# FiltreFSK.net
KiCad netlist of a schematic drawn in EAGLE
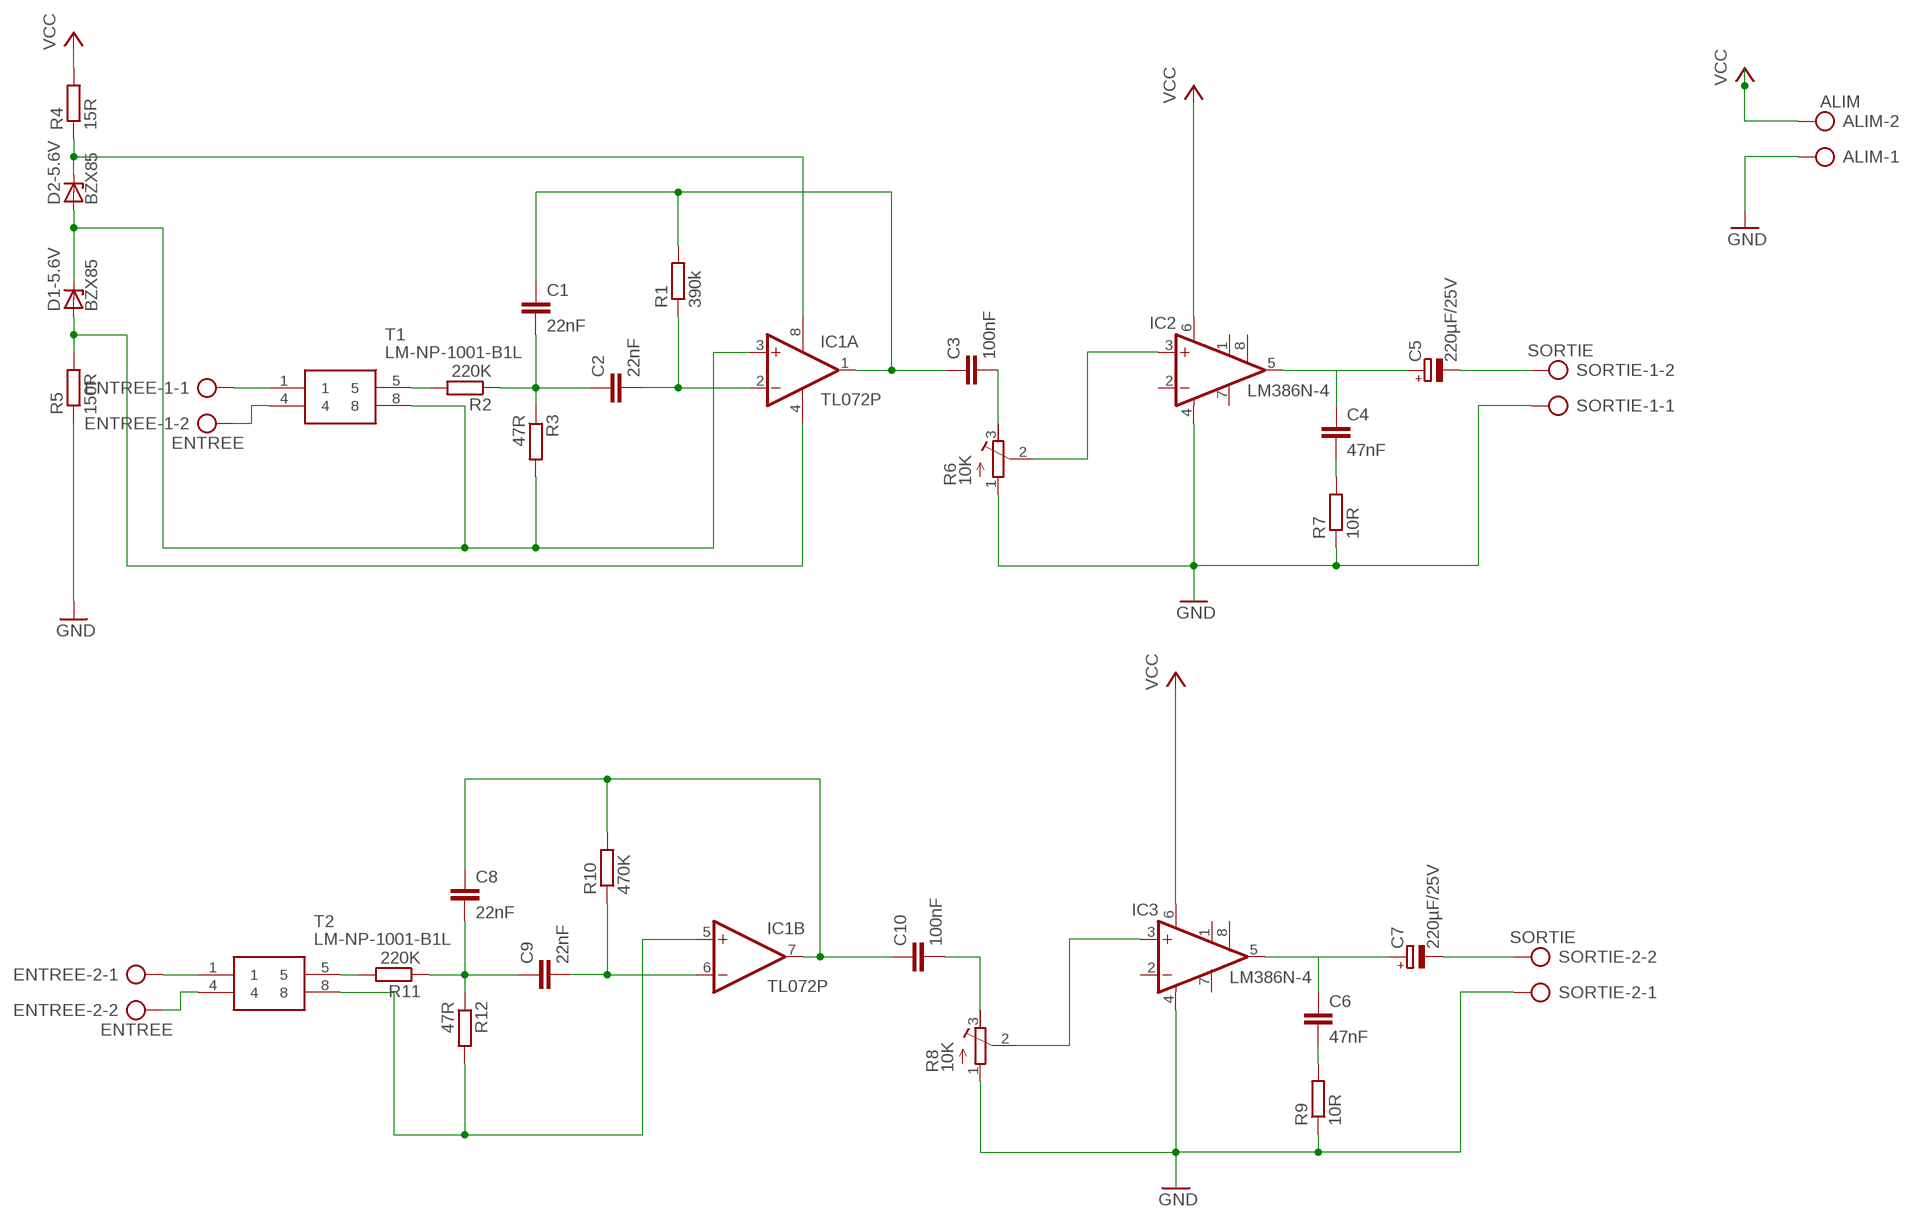
[diagram p0: schematic, sheet 1]

(export (version "E")
  (design (tool "Eeschema 10.0.6"))
  (components
    (comp (ref "ALIM")
      (value "ALIM")
      (footprint "eagle-import:AK500_2-H")
      (libsource (lib "eagle-import") (part "AK500/2-H"))
    )
    (comp (ref "C1")
      (value "22nF")
      (footprint "eagle-import:C050-025X075")
      (libsource (lib "eagle-import") (part "C-EU050-025X075"))
    )
    (comp (ref "C2")
      (value "22nF")
      (footprint "eagle-import:C050-025X075")
      (libsource (lib "eagle-import") (part "C-EU050-025X075"))
    )
    (comp (ref "C3")
      (value "100nF")
      (footprint "eagle-import:C075-042X103")
      (libsource (lib "eagle-import") (part "C-EU075-042X103"))
    )
    (comp (ref "C4")
      (value "47nF")
      (footprint "eagle-import:C050-025X075")
      (libsource (lib "eagle-import") (part "C-EU050-025X075"))
    )
    (comp (ref "C5")
      (value "220µF/25V")
      (footprint "eagle-import:E3,5-8")
      (libsource (lib "eagle-import") (part "CPOL-EUE3.5-8"))
    )
    (comp (ref "C6")
      (value "47nF")
      (footprint "eagle-import:C050-025X075")
      (libsource (lib "eagle-import") (part "C-EU050-025X075"))
    )
    (comp (ref "C7")
      (value "220µF/25V")
      (footprint "eagle-import:E3,5-8")
      (libsource (lib "eagle-import") (part "CPOL-EUE3.5-8"))
    )
    (comp (ref "C8")
      (value "22nF")
      (footprint "eagle-import:C050-025X075")
      (libsource (lib "eagle-import") (part "C-EU050-025X075"))
    )
    (comp (ref "C9")
      (value "22nF")
      (footprint "eagle-import:C050-025X075")
      (libsource (lib "eagle-import") (part "C-EU050-025X075"))
    )
    (comp (ref "C10")
      (value "100nF")
      (footprint "eagle-import:C075-042X103")
      (libsource (lib "eagle-import") (part "C-EU075-042X103"))
    )
    (comp (ref "D1-5.6V")
      (value "BZX85")
      (footprint "eagle-import:DO41Z10")
      (libsource (lib "eagle-import") (part "BZX85"))
    )
    (comp (ref "D2-5.6V")
      (value "BZX85")
      (footprint "eagle-import:DO41Z10")
      (libsource (lib "eagle-import") (part "BZX85"))
    )
    (comp (ref "ENTREE-1")
      (value "ENTREE")
      (footprint "eagle-import:AK500_2-H")
      (libsource (lib "eagle-import") (part "AK500/2-H"))
    )
    (comp (ref "ENTREE-2")
      (value "ENTREE")
      (footprint "eagle-import:AK500_2-H")
      (libsource (lib "eagle-import") (part "AK500/2-H"))
    )
    (comp (ref "IC1")
      (value "TL072P")
      (footprint "eagle-import:DIL08")
      (libsource (lib "eagle-import") (part "TL072P"))
    )
    (comp (ref "IC2")
      (value "LM386N-4")
      (footprint "eagle-import:DIL08")
      (libsource (lib "eagle-import") (part "LM386?-N4"))
    )
    (comp (ref "IC3")
      (value "LM386N-4")
      (footprint "eagle-import:DIL08")
      (libsource (lib "eagle-import") (part "LM386?-N4"))
    )
    (comp (ref "R1")
      (value "390k")
      (footprint "eagle-import:0207_10")
      (libsource (lib "eagle-import") (part "R-EU_0207/10"))
    )
    (comp (ref "R2")
      (value "220K")
      (footprint "eagle-import:0207_10")
      (libsource (lib "eagle-import") (part "R-EU_0207/10"))
    )
    (comp (ref "R3")
      (value "47R")
      (footprint "eagle-import:0207_10")
      (libsource (lib "eagle-import") (part "R-EU_0207/10"))
    )
    (comp (ref "R4")
      (value "15R")
      (footprint "eagle-import:0207_10")
      (libsource (lib "eagle-import") (part "R-EU_0207/10"))
    )
    (comp (ref "R5")
      (value "150R")
      (footprint "eagle-import:0207_10")
      (libsource (lib "eagle-import") (part "R-EU_0207/10"))
    )
    (comp (ref "R6")
      (value "10K")
      (footprint "eagle-import:RTRIM3339P")
      (libsource (lib "eagle-import") (part "R-TRIMM3339P"))
    )
    (comp (ref "R7")
      (value "10R")
      (footprint "eagle-import:0207_10")
      (libsource (lib "eagle-import") (part "R-EU_0207/10"))
    )
    (comp (ref "R8")
      (value "10K")
      (footprint "eagle-import:RTRIM3339P")
      (libsource (lib "eagle-import") (part "R-TRIMM3339P"))
    )
    (comp (ref "R9")
      (value "10R")
      (footprint "eagle-import:0207_10")
      (libsource (lib "eagle-import") (part "R-EU_0207/10"))
    )
    (comp (ref "R10")
      (value "470K")
      (footprint "eagle-import:0207_10")
      (libsource (lib "eagle-import") (part "R-EU_0207/10"))
    )
    (comp (ref "R11")
      (value "220K")
      (footprint "eagle-import:0207_10")
      (libsource (lib "eagle-import") (part "R-EU_0207/10"))
    )
    (comp (ref "R12")
      (value "47R")
      (footprint "eagle-import:0207_10")
      (libsource (lib "eagle-import") (part "R-EU_0207/10"))
    )
    (comp (ref "SORTIE-1")
      (value "SORTIE")
      (footprint "eagle-import:AK500_2-H")
      (libsource (lib "eagle-import") (part "AK500/2-H"))
    )
    (comp (ref "SORTIE-2")
      (value "SORTIE")
      (footprint "eagle-import:AK500_2-H")
      (libsource (lib "eagle-import") (part "AK500/2-H"))
    )
    (comp (ref "T1")
      (value "LM-NP-1001-B1L")
      (footprint "eagle-import:LMNP1001B1L")
      (fields
        (field (name "MOUSER_PART_NUMBER") "652-LM-NP-1001-B1L")
        (field (name "RS_PART_NUMBER") "1740620")
      )
      (libsource (lib "eagle-import") (part "LM-NP-1001-B1L"))
    )
    (comp (ref "T2")
      (value "LM-NP-1001-B1L")
      (footprint "eagle-import:LMNP1001B1L")
      (fields
        (field (name "MOUSER_PART_NUMBER") "652-LM-NP-1001-B1L")
        (field (name "RS_PART_NUMBER") "1740620")
      )
      (libsource (lib "eagle-import") (part "LM-NP-1001-B1L"))
    )
  )
  (nets
    (net (code "1") (name "GND") (class "Default")
      (node (ref "ALIM") (pin "1") (pinfunction "KL_1") (pintype "passive"))
      (node (ref "IC2") (pin "4") (pinfunction "GND_4") (pintype "power_in"))
      (node (ref "IC3") (pin "4") (pinfunction "GND_4") (pintype "power_in"))
      (node (ref "R5") (pin "1") (pinfunction "1_1") (pintype "passive"))
      (node (ref "R6") (pin "1") (pinfunction "A_1") (pintype "passive"))
      (node (ref "R7") (pin "1") (pinfunction "1_1") (pintype "passive"))
      (node (ref "R8") (pin "1") (pinfunction "A_1") (pintype "passive"))
      (node (ref "R9") (pin "1") (pinfunction "1_1") (pintype "passive"))
      (node (ref "SORTIE-1") (pin "1") (pinfunction "KL_1") (pintype "passive"))
      (node (ref "SORTIE-2") (pin "1") (pinfunction "KL_1") (pintype "passive"))
    )
    (net (code "2") (name "Net-(C1-Pad2)") (class "Default")
      (node (ref "C1") (pin "2") (pinfunction "2_2") (pintype "passive"))
      (node (ref "C2") (pin "1") (pinfunction "1_1") (pintype "passive"))
      (node (ref "R2") (pin "1") (pinfunction "1_1") (pintype "passive"))
      (node (ref "R3") (pin "1") (pinfunction "1_1") (pintype "passive"))
    )
    (net (code "3") (name "Net-(C4-Pad2)") (class "Default")
      (node (ref "C4") (pin "2") (pinfunction "2_2") (pintype "passive"))
      (node (ref "R7") (pin "2") (pinfunction "2_2") (pintype "passive"))
    )
    (net (code "4") (name "Net-(C6-Pad2)") (class "Default")
      (node (ref "C6") (pin "2") (pinfunction "2_2") (pintype "passive"))
      (node (ref "R9") (pin "2") (pinfunction "2_2") (pintype "passive"))
    )
    (net (code "5") (name "Net-(C8-Pad2)") (class "Default")
      (node (ref "C8") (pin "2") (pinfunction "2_2") (pintype "passive"))
      (node (ref "C9") (pin "1") (pinfunction "1_1") (pintype "passive"))
      (node (ref "R11") (pin "1") (pinfunction "1_1") (pintype "passive"))
      (node (ref "R12") (pin "1") (pinfunction "1_1") (pintype "passive"))
    )
    (net (code "6") (name "Net-(ENTREE-1A-KL)") (class "Default")
      (node (ref "ENTREE-1") (pin "1") (pinfunction "KL_1") (pintype "passive"))
      (node (ref "T1") (pin "1") (pinfunction "1_1") (pintype "bidirectional"))
    )
    (net (code "7") (name "Net-(ENTREE-1B-KL)") (class "Default")
      (node (ref "ENTREE-1") (pin "2") (pinfunction "KL_2") (pintype "passive"))
      (node (ref "T1") (pin "4") (pinfunction "4_4") (pintype "bidirectional"))
    )
    (net (code "8") (name "Net-(ENTREE-2A-KL)") (class "Default")
      (node (ref "ENTREE-2") (pin "1") (pinfunction "KL_1") (pintype "passive"))
      (node (ref "T2") (pin "1") (pinfunction "1_1") (pintype "bidirectional"))
    )
    (net (code "9") (name "Net-(ENTREE-2B-KL)") (class "Default")
      (node (ref "ENTREE-2") (pin "2") (pinfunction "KL_2") (pintype "passive"))
      (node (ref "T2") (pin "4") (pinfunction "4_4") (pintype "bidirectional"))
    )
    (net (code "10") (name "Net-(IC1A-+IN)") (class "Default")
      (node (ref "D1-5.6V") (pin "C") (pinfunction "C_C") (pintype "passive"))
      (node (ref "D2-5.6V") (pin "A") (pinfunction "A_A") (pintype "passive"))
      (node (ref "IC1") (pin "3") (pinfunction "+IN_3") (pintype "input"))
      (node (ref "R3") (pin "2") (pinfunction "2_2") (pintype "passive"))
      (node (ref "T1") (pin "8") (pinfunction "8_8") (pintype "bidirectional"))
    )
    (net (code "11") (name "Net-(IC1A--IN)") (class "Default")
      (node (ref "C2") (pin "2") (pinfunction "2_2") (pintype "passive"))
      (node (ref "IC1") (pin "2") (pinfunction "-IN_2") (pintype "input"))
      (node (ref "R1") (pin "1") (pinfunction "1_1") (pintype "passive"))
    )
    (net (code "12") (name "Net-(IC1A-OUT)") (class "Default")
      (node (ref "C1") (pin "1") (pinfunction "1_1") (pintype "passive"))
      (node (ref "C3") (pin "1") (pinfunction "1_1") (pintype "passive"))
      (node (ref "IC1") (pin "1") (pinfunction "OUT_1") (pintype "output"))
      (node (ref "R1") (pin "2") (pinfunction "2_2") (pintype "passive"))
    )
    (net (code "13") (name "Net-(IC1B-+IN)") (class "Default")
      (node (ref "IC1") (pin "5") (pinfunction "+IN_5") (pintype "input"))
      (node (ref "R12") (pin "2") (pinfunction "2_2") (pintype "passive"))
      (node (ref "T2") (pin "8") (pinfunction "8_8") (pintype "bidirectional"))
    )
    (net (code "14") (name "Net-(IC1B--IN)") (class "Default")
      (node (ref "C9") (pin "2") (pinfunction "2_2") (pintype "passive"))
      (node (ref "IC1") (pin "6") (pinfunction "-IN_6") (pintype "input"))
      (node (ref "R10") (pin "1") (pinfunction "1_1") (pintype "passive"))
    )
    (net (code "15") (name "Net-(IC1B-OUT)") (class "Default")
      (node (ref "C10") (pin "1") (pinfunction "1_1") (pintype "passive"))
      (node (ref "C8") (pin "1") (pinfunction "1_1") (pintype "passive"))
      (node (ref "IC1") (pin "7") (pinfunction "OUT_7") (pintype "output"))
      (node (ref "R10") (pin "2") (pinfunction "2_2") (pintype "passive"))
    )
    (net (code "16") (name "Net-(IC1C-V+)") (class "Default")
      (node (ref "D2-5.6V") (pin "C") (pinfunction "C_C") (pintype "passive"))
      (node (ref "IC1") (pin "8") (pinfunction "V+_8") (pintype "power_in"))
      (node (ref "R4") (pin "1") (pinfunction "1_1") (pintype "passive"))
    )
    (net (code "17") (name "Net-(IC1C-V-)") (class "Default")
      (node (ref "D1-5.6V") (pin "A") (pinfunction "A_A") (pintype "passive"))
      (node (ref "IC1") (pin "4") (pinfunction "V-_4") (pintype "power_in"))
      (node (ref "R5") (pin "2") (pinfunction "2_2") (pintype "passive"))
    )
    (net (code "18") (name "Net-(IC2-+IN)") (class "Default")
      (node (ref "IC2") (pin "3") (pinfunction "+IN_3") (pintype "input"))
      (node (ref "R6") (pin "2") (pinfunction "S_2") (pintype "passive"))
    )
    (net (code "19") (name "Net-(IC2-OUT)") (class "Default")
      (node (ref "C4") (pin "1") (pinfunction "1_1") (pintype "passive"))
      (node (ref "C5") (pin "+") (pinfunction "+_+") (pintype "passive"))
      (node (ref "IC2") (pin "5") (pinfunction "OUT_5") (pintype "output"))
    )
    (net (code "20") (name "Net-(IC3-+IN)") (class "Default")
      (node (ref "IC3") (pin "3") (pinfunction "+IN_3") (pintype "input"))
      (node (ref "R8") (pin "2") (pinfunction "S_2") (pintype "passive"))
    )
    (net (code "21") (name "Net-(IC3-OUT)") (class "Default")
      (node (ref "C6") (pin "1") (pinfunction "1_1") (pintype "passive"))
      (node (ref "C7") (pin "+") (pinfunction "+_+") (pintype "passive"))
      (node (ref "IC3") (pin "5") (pinfunction "OUT_5") (pintype "output"))
    )
    (net (code "22") (name "Net-(R2-Pad2)") (class "Default")
      (node (ref "R2") (pin "2") (pinfunction "2_2") (pintype "passive"))
      (node (ref "T1") (pin "5") (pinfunction "5_5") (pintype "bidirectional"))
    )
    (net (code "23") (name "Net-(R6-E)") (class "Default")
      (node (ref "C3") (pin "2") (pinfunction "2_2") (pintype "passive"))
      (node (ref "R6") (pin "3") (pinfunction "E_3") (pintype "passive"))
    )
    (net (code "24") (name "Net-(R8-E)") (class "Default")
      (node (ref "C10") (pin "2") (pinfunction "2_2") (pintype "passive"))
      (node (ref "R8") (pin "3") (pinfunction "E_3") (pintype "passive"))
    )
    (net (code "25") (name "Net-(R11-Pad2)") (class "Default")
      (node (ref "R11") (pin "2") (pinfunction "2_2") (pintype "passive"))
      (node (ref "T2") (pin "5") (pinfunction "5_5") (pintype "bidirectional"))
    )
    (net (code "26") (name "Net-(SORTIE-1B-KL)") (class "Default")
      (node (ref "C5") (pin "-") (pinfunction "-_-") (pintype "passive"))
      (node (ref "SORTIE-1") (pin "2") (pinfunction "KL_2") (pintype "passive"))
    )
    (net (code "27") (name "Net-(SORTIE-2B-KL)") (class "Default")
      (node (ref "C7") (pin "-") (pinfunction "-_-") (pintype "passive"))
      (node (ref "SORTIE-2") (pin "2") (pinfunction "KL_2") (pintype "passive"))
    )
    (net (code "28") (name "VCC") (class "Default")
      (node (ref "ALIM") (pin "2") (pinfunction "KL_2") (pintype "passive"))
      (node (ref "IC2") (pin "6") (pinfunction "VS_6") (pintype "power_in"))
      (node (ref "IC3") (pin "6") (pinfunction "VS_6") (pintype "power_in"))
      (node (ref "R4") (pin "2") (pinfunction "2_2") (pintype "passive"))
    )
    (net (code "29") (name "unconnected-(IC2--IN-Pad2)") (class "Default")
      (node (ref "IC2") (pin "2") (pinfunction "-IN_2") (pintype "input"))
    )
    (net (code "30") (name "unconnected-(IC2-BYPASS-Pad7)") (class "Default")
      (node (ref "IC2") (pin "7") (pinfunction "BYPASS_7") (pintype "passive"))
    )
    (net (code "31") (name "unconnected-(IC2-GAIN-Pad1)") (class "Default")
      (node (ref "IC2") (pin "1") (pinfunction "GAIN_1") (pintype "passive"))
    )
    (net (code "32") (name "unconnected-(IC2-GAIN-Pad8)") (class "Default")
      (node (ref "IC2") (pin "8") (pinfunction "GAIN_8") (pintype "passive"))
    )
    (net (code "33") (name "unconnected-(IC3--IN-Pad2)") (class "Default")
      (node (ref "IC3") (pin "2") (pinfunction "-IN_2") (pintype "input"))
    )
    (net (code "34") (name "unconnected-(IC3-BYPASS-Pad7)") (class "Default")
      (node (ref "IC3") (pin "7") (pinfunction "BYPASS_7") (pintype "passive"))
    )
    (net (code "35") (name "unconnected-(IC3-GAIN-Pad1)") (class "Default")
      (node (ref "IC3") (pin "1") (pinfunction "GAIN_1") (pintype "passive"))
    )
    (net (code "36") (name "unconnected-(IC3-GAIN-Pad8)") (class "Default")
      (node (ref "IC3") (pin "8") (pinfunction "GAIN_8") (pintype "passive"))
    )
  )
)
